# Encoder.net
KiCad netlist of a schematic drawn in EAGLE
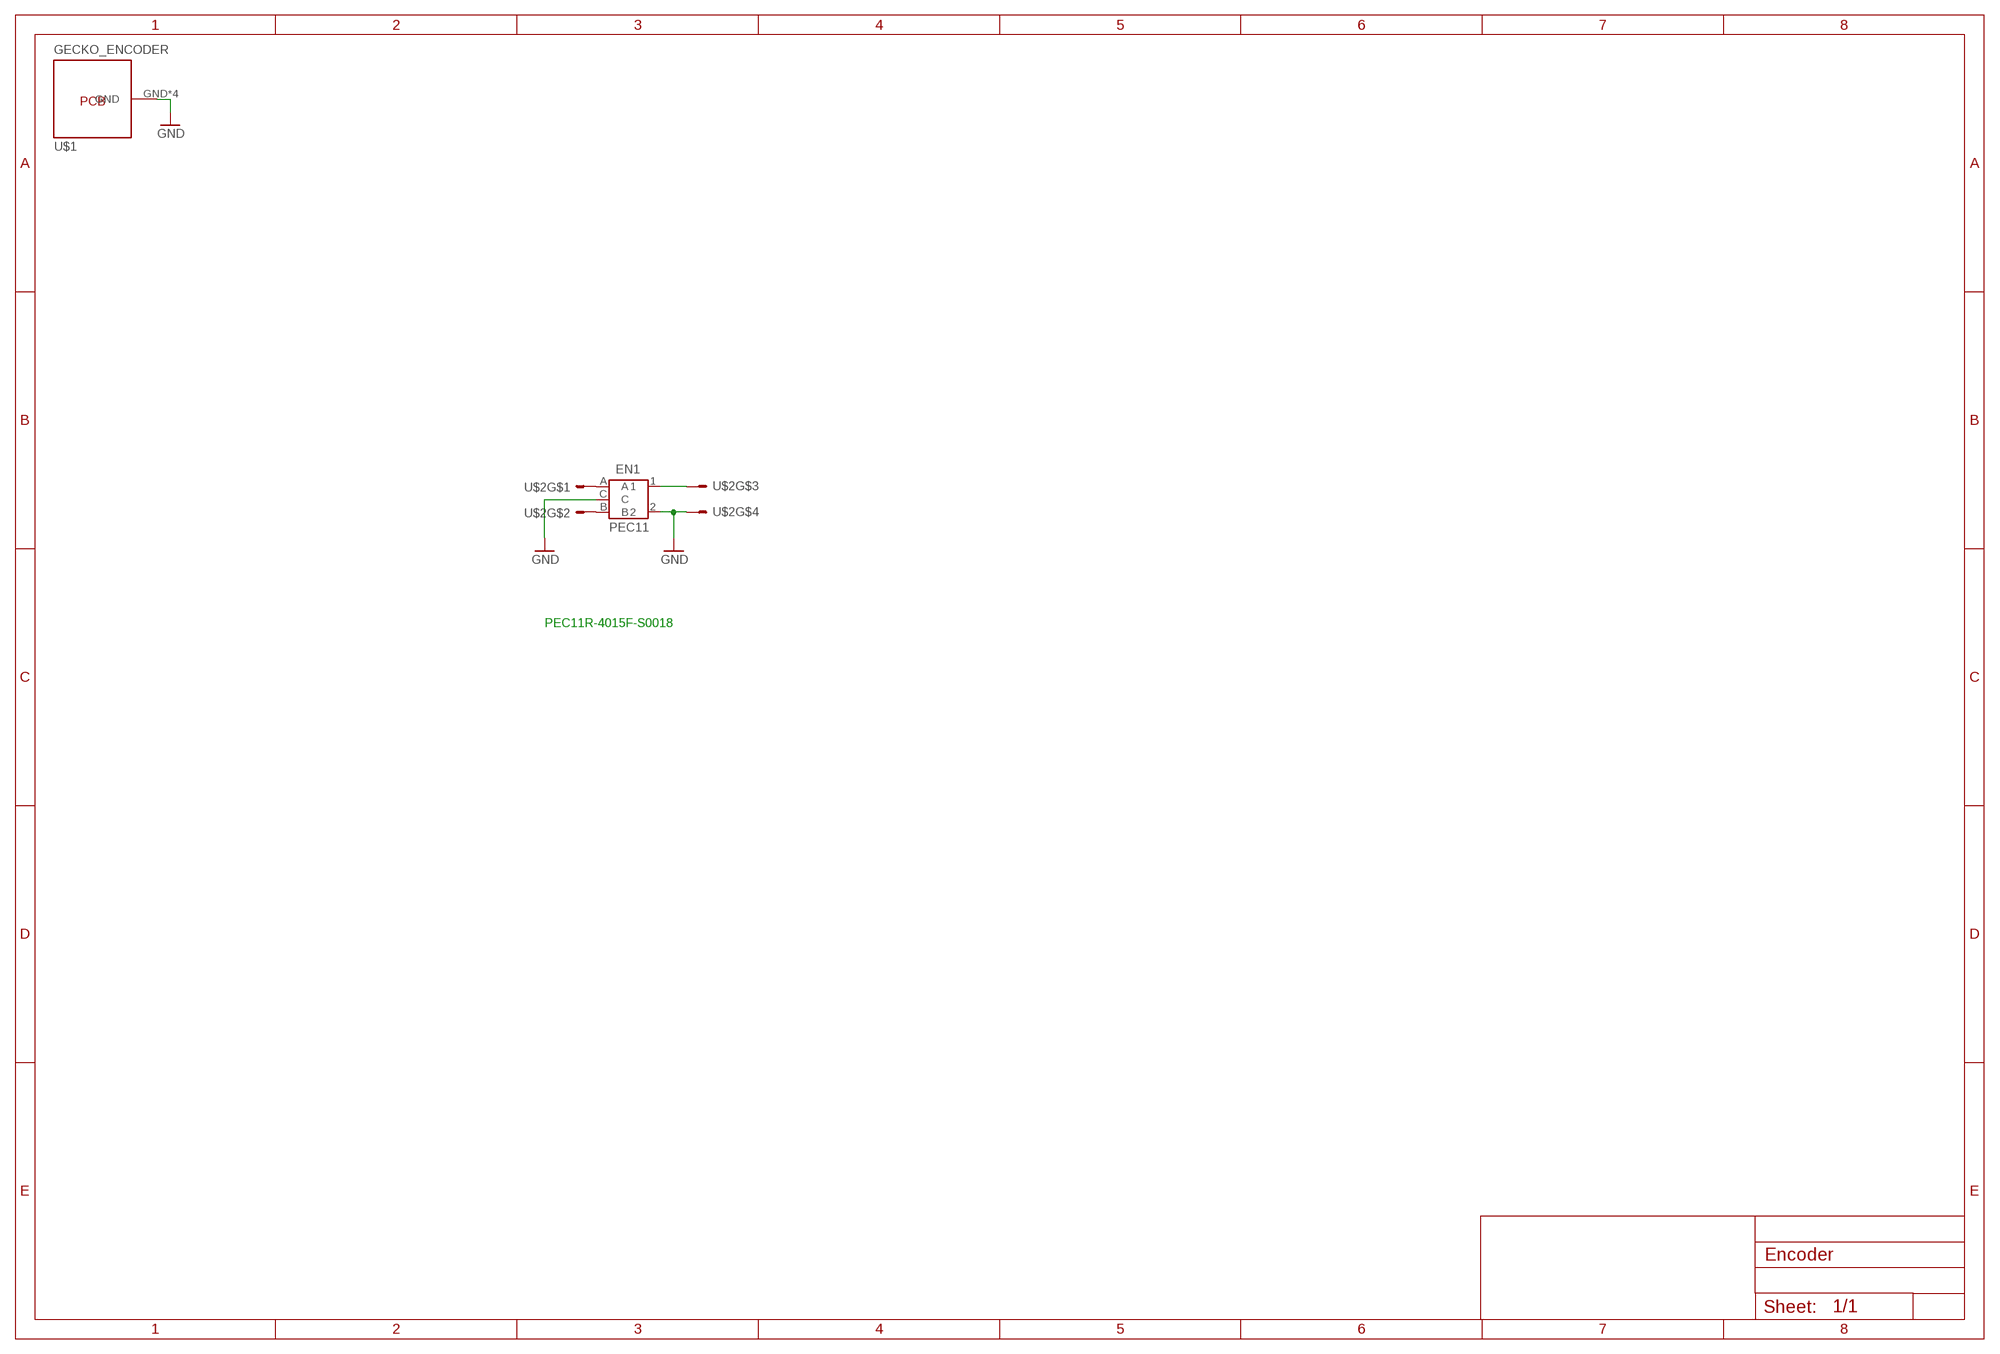
[diagram p0: schematic, sheet 1]

(export (version "E")
  (design (tool "Eeschema 10.0.6"))
  (components
    (comp (ref "EN1")
      (value "PEC11")
      (footprint "eagle-import:PEC11_4XXXXK-S")
      (libsource (lib "eagle-import") (part "PEC11"))
    )
    (comp (ref "U$1")
      (value "GECKO_ENCODER")
      (footprint "eagle-import:GECKO_ENCODER")
      (libsource (lib "eagle-import") (part "GECKO_ENCODER"))
    )
    (comp (ref "U$2")
      (value "JST-SH-4-SMT")
      (footprint "eagle-import:JST-SH-4-SMT")
      (libsource (lib "eagle-import") (part "JST-SH-4-SMT"))
    )
  )
  (nets
    (net (code "1") (name "GND") (class "Default")
      (node (ref "EN1") (pin "2") (pinfunction "2_2") (pintype "passive"))
      (node (ref "EN1") (pin "C") (pinfunction "C_C") (pintype "passive"))
      (node (ref "U$1") (pin "GND") (pinfunction "GND_GND") (pintype "bidirectional"))
      (node (ref "U$1") (pin "GND1") (pinfunction "GND_GND1") (pintype "bidirectional"))
      (node (ref "U$1") (pin "GND2") (pinfunction "GND_GND2") (pintype "bidirectional"))
      (node (ref "U$1") (pin "GND3") (pinfunction "GND_GND3") (pintype "bidirectional"))
      (node (ref "U$2") (pin "P$4") (pinfunction "S_P$4") (pintype "passive"))
    )
    (net (code "2") (name "Net-(U$2A-S)") (class "Default")
      (node (ref "EN1") (pin "A") (pinfunction "A_A") (pintype "passive"))
      (node (ref "U$2") (pin "P$1") (pinfunction "S_P$1") (pintype "passive"))
    )
    (net (code "3") (name "Net-(U$2B-S)") (class "Default")
      (node (ref "EN1") (pin "B") (pinfunction "B_B") (pintype "passive"))
      (node (ref "U$2") (pin "P$2") (pinfunction "S_P$2") (pintype "passive"))
    )
    (net (code "4") (name "Net-(U$2C-S)") (class "Default")
      (node (ref "EN1") (pin "1") (pinfunction "1_1") (pintype "passive"))
      (node (ref "U$2") (pin "P$3") (pinfunction "S_P$3") (pintype "passive"))
    )
  )
)
